# MIPI_CSI-2.net
KiCad netlist of a schematic drawn in Altium Designer
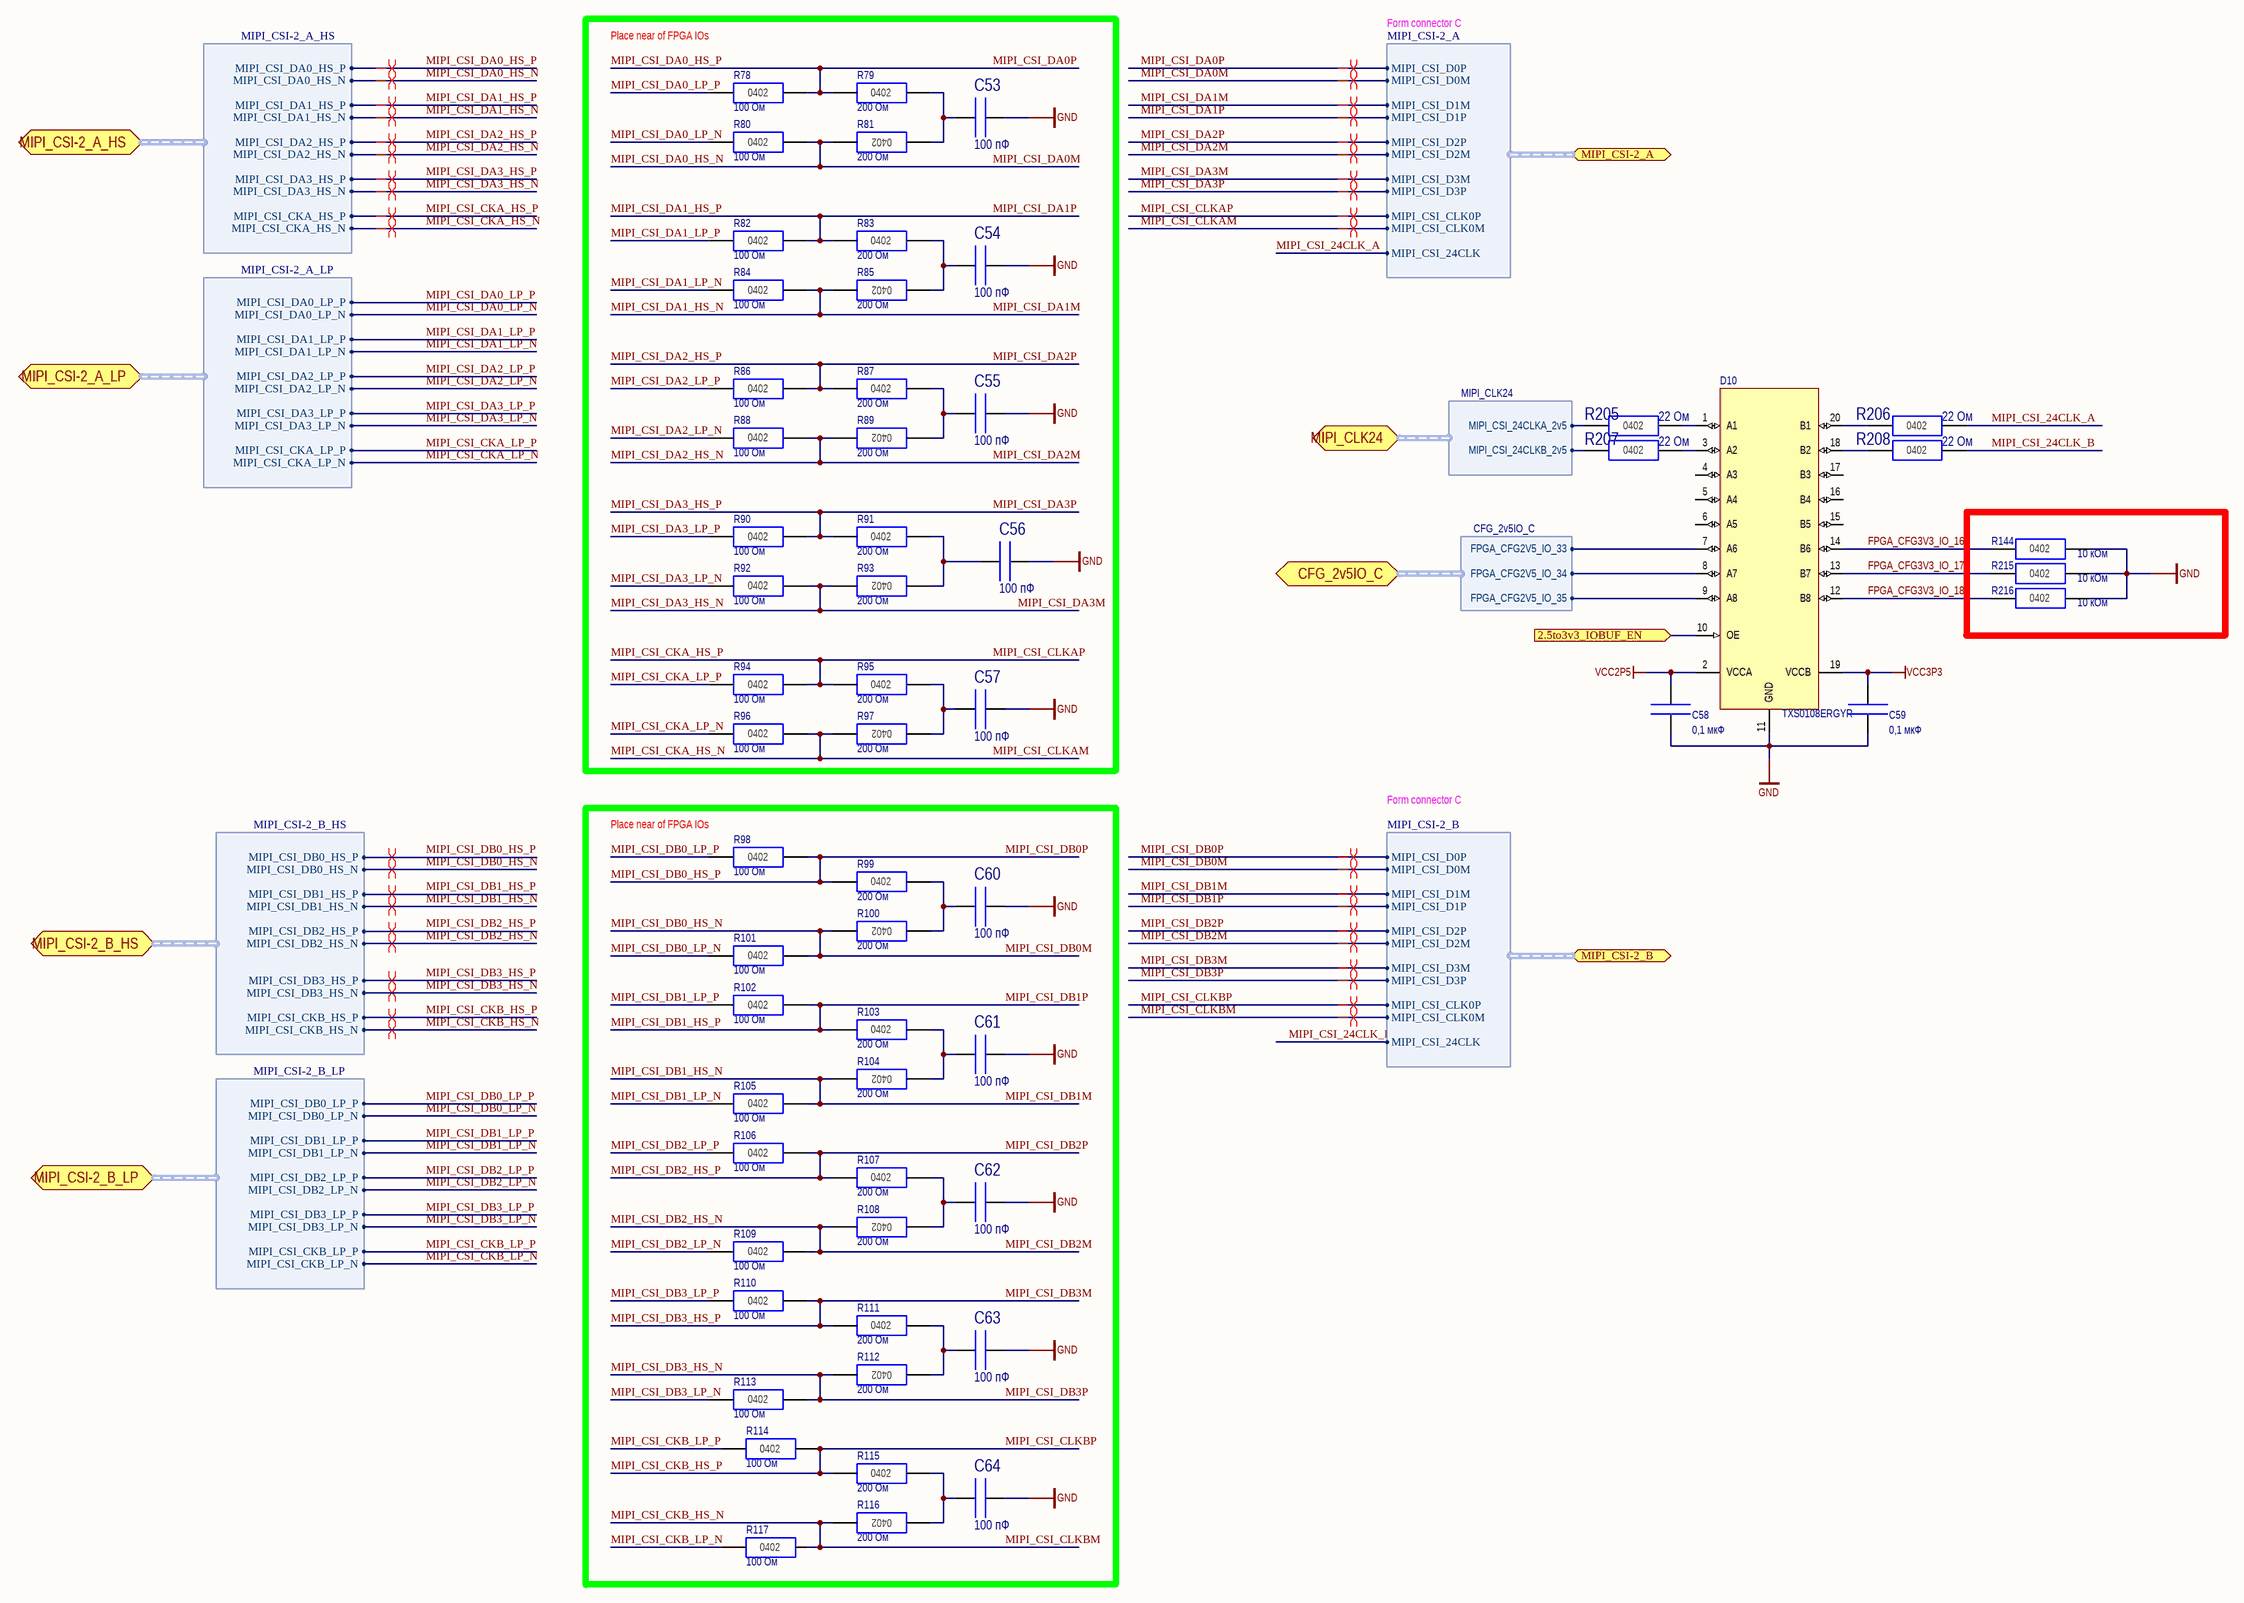
[diagram p0: MIPI_CSI-2.SchDoc]

(export (version "E")
  (design (tool "Eeschema 10.0.6"))
  (components
    (comp (ref "C53")
      (value "100 пФ")
      (footprint "CC0402(1005)")
      (description "Чип конденсатор керамический")
      (fields (field (name "Comment") "CC0402-NP0-100 пФ-1%-50В"))
      (libsource (lib "Чип конденсаторы") (part "CC0402-X7R-#-20%-10В"))
    )
    (comp (ref "C54")
      (value "100 пФ")
      (footprint "CC0402(1005)")
      (description "Чип конденсатор керамический")
      (fields (field (name "Comment") "CC0402-NP0-100 пФ-1%-50В"))
      (libsource (lib "Чип конденсаторы") (part "CC0402-X7R-#-20%-10В"))
    )
    (comp (ref "C55")
      (value "100 пФ")
      (footprint "CC0402(1005)")
      (description "Чип конденсатор керамический")
      (fields (field (name "Comment") "CC0402-NP0-100 пФ-1%-50В"))
      (libsource (lib "Чип конденсаторы") (part "CC0402-X7R-#-20%-10В"))
    )
    (comp (ref "C56")
      (value "100 пФ")
      (footprint "CC0402(1005)")
      (description "Чип конденсатор керамический")
      (fields (field (name "Comment") "CC0402-NP0-100 пФ-1%-50В"))
      (libsource (lib "Чип конденсаторы") (part "CC0402-X7R-#-20%-10В"))
    )
    (comp (ref "C57")
      (value "100 пФ")
      (footprint "CC0402(1005)")
      (description "Чип конденсатор керамический")
      (fields (field (name "Comment") "CC0402-NP0-100 пФ-1%-50В"))
      (libsource (lib "Чип конденсаторы") (part "CC0402-X7R-#-20%-10В"))
    )
    (comp (ref "C58")
      (value "0,1 мкФ")
      (footprint "CC0402(1005)")
      (description "Чип конденсатор керамический")
      (fields (field (name "Comment") "CC0402-X7R-0,1 мкФ-20%-10В"))
      (libsource (lib "Чип конденсаторы") (part "CC0402-X7R-#-20%-10В"))
    )
    (comp (ref "C59")
      (value "0,1 мкФ")
      (footprint "CC0402(1005)")
      (description "Чип конденсатор керамический")
      (fields (field (name "Comment") "CC0402-X7R-0,1 мкФ-20%-10В"))
      (libsource (lib "Чип конденсаторы") (part "CC0402-X7R-#-20%-10В"))
    )
    (comp (ref "C60")
      (value "100 пФ")
      (footprint "CC0402(1005)")
      (description "Чип конденсатор керамический")
      (fields (field (name "Comment") "CC0402-NP0-100 пФ-1%-50В"))
      (libsource (lib "Чип конденсаторы") (part "CC0402-X7R-#-20%-10В"))
    )
    (comp (ref "C61")
      (value "100 пФ")
      (footprint "CC0402(1005)")
      (description "Чип конденсатор керамический")
      (fields (field (name "Comment") "CC0402-NP0-100 пФ-1%-50В"))
      (libsource (lib "Чип конденсаторы") (part "CC0402-X7R-#-20%-10В"))
    )
    (comp (ref "C62")
      (value "100 пФ")
      (footprint "CC0402(1005)")
      (description "Чип конденсатор керамический")
      (fields (field (name "Comment") "CC0402-NP0-100 пФ-1%-50В"))
      (libsource (lib "Чип конденсаторы") (part "CC0402-X7R-#-20%-10В"))
    )
    (comp (ref "C63")
      (value "100 пФ")
      (footprint "CC0402(1005)")
      (description "Чип конденсатор керамический")
      (fields (field (name "Comment") "CC0402-NP0-100 пФ-1%-50В"))
      (libsource (lib "Чип конденсаторы") (part "CC0402-X7R-#-20%-10В"))
    )
    (comp (ref "C64")
      (value "100 пФ")
      (footprint "CC0402(1005)")
      (description "Чип конденсатор керамический")
      (fields (field (name "Comment") "CC0402-NP0-100 пФ-1%-50В"))
      (libsource (lib "Чип конденсаторы") (part "CC0402-X7R-#-20%-10В"))
    )
    (comp (ref "D10")
      (value "TXS0108ERGYR")
      (footprint "QFN50P450X350X100_HS-21N")
      (fields
        (field (name "GENERIC PART NUMBER") "TXB0108")
        (field (name "MANUFACTURER") "Texas Instruments")
      )
      (libsource (lib "SD_IC") (part "TXS0108ERGYR"))
    )
    (comp (ref "R78")
      (value "100 Ом")
      (footprint "CR0402(1005)")
      (description "Чип резистор")
      (fields (field (name "TOLERANCE") "5%") (field (name "Comment") "CR0402-100 Ом-±5%"))
      (libsource (lib "Резисторы") (part "CR0402-#-±5%"))
    )
    (comp (ref "R79")
      (value "200 Ом")
      (footprint "CR0402(1005)")
      (description "Чип резистор")
      (fields (field (name "TOLERANCE") "5%") (field (name "Comment") "CR0402-200 Ом-±5%"))
      (libsource (lib "Резисторы") (part "CR0402-#-±5%"))
    )
    (comp (ref "R80")
      (value "100 Ом")
      (footprint "CR0402(1005)")
      (description "Чип резистор")
      (fields (field (name "TOLERANCE") "5%") (field (name "Comment") "CR0402-100 Ом-±5%"))
      (libsource (lib "Резисторы") (part "CR0402-#-±5%"))
    )
    (comp (ref "R81")
      (value "200 Ом")
      (footprint "CR0402(1005)")
      (description "Чип резистор")
      (fields (field (name "TOLERANCE") "5%") (field (name "Comment") "CR0402-200 Ом-±5%"))
      (libsource (lib "") (part "CR0402-#-±5%_1"))
    )
    (comp (ref "R82")
      (value "100 Ом")
      (footprint "CR0402(1005)")
      (description "Чип резистор")
      (fields (field (name "TOLERANCE") "5%") (field (name "Comment") "CR0402-100 Ом-±5%"))
      (libsource (lib "Резисторы") (part "CR0402-#-±5%"))
    )
    (comp (ref "R83")
      (value "200 Ом")
      (footprint "CR0402(1005)")
      (description "Чип резистор")
      (fields (field (name "TOLERANCE") "5%") (field (name "Comment") "CR0402-200 Ом-±5%"))
      (libsource (lib "Резисторы") (part "CR0402-#-±5%"))
    )
    (comp (ref "R84")
      (value "100 Ом")
      (footprint "CR0402(1005)")
      (description "Чип резистор")
      (fields (field (name "TOLERANCE") "5%") (field (name "Comment") "CR0402-100 Ом-±5%"))
      (libsource (lib "Резисторы") (part "CR0402-#-±5%"))
    )
    (comp (ref "R85")
      (value "200 Ом")
      (footprint "CR0402(1005)")
      (description "Чип резистор")
      (fields (field (name "TOLERANCE") "5%") (field (name "Comment") "CR0402-200 Ом-±5%"))
      (libsource (lib "") (part "CR0402-#-±5%_1"))
    )
    (comp (ref "R86")
      (value "100 Ом")
      (footprint "CR0402(1005)")
      (description "Чип резистор")
      (fields (field (name "TOLERANCE") "5%") (field (name "Comment") "CR0402-100 Ом-±5%"))
      (libsource (lib "Резисторы") (part "CR0402-#-±5%"))
    )
    (comp (ref "R87")
      (value "200 Ом")
      (footprint "CR0402(1005)")
      (description "Чип резистор")
      (fields (field (name "TOLERANCE") "5%") (field (name "Comment") "CR0402-200 Ом-±5%"))
      (libsource (lib "Резисторы") (part "CR0402-#-±5%"))
    )
    (comp (ref "R88")
      (value "100 Ом")
      (footprint "CR0402(1005)")
      (description "Чип резистор")
      (fields (field (name "TOLERANCE") "5%") (field (name "Comment") "CR0402-100 Ом-±5%"))
      (libsource (lib "Резисторы") (part "CR0402-#-±5%"))
    )
    (comp (ref "R89")
      (value "200 Ом")
      (footprint "CR0402(1005)")
      (description "Чип резистор")
      (fields (field (name "TOLERANCE") "5%") (field (name "Comment") "CR0402-200 Ом-±5%"))
      (libsource (lib "") (part "CR0402-#-±5%_1"))
    )
    (comp (ref "R90")
      (value "100 Ом")
      (footprint "CR0402(1005)")
      (description "Чип резистор")
      (fields (field (name "TOLERANCE") "5%") (field (name "Comment") "CR0402-100 Ом-±5%"))
      (libsource (lib "Резисторы") (part "CR0402-#-±5%"))
    )
    (comp (ref "R91")
      (value "200 Ом")
      (footprint "CR0402(1005)")
      (description "Чип резистор")
      (fields (field (name "TOLERANCE") "5%") (field (name "Comment") "CR0402-200 Ом-±5%"))
      (libsource (lib "Резисторы") (part "CR0402-#-±5%"))
    )
    (comp (ref "R92")
      (value "100 Ом")
      (footprint "CR0402(1005)")
      (description "Чип резистор")
      (fields (field (name "TOLERANCE") "5%") (field (name "Comment") "CR0402-100 Ом-±5%"))
      (libsource (lib "Резисторы") (part "CR0402-#-±5%"))
    )
    (comp (ref "R93")
      (value "200 Ом")
      (footprint "CR0402(1005)")
      (description "Чип резистор")
      (fields (field (name "TOLERANCE") "5%") (field (name "Comment") "CR0402-200 Ом-±5%"))
      (libsource (lib "") (part "CR0402-#-±5%_1"))
    )
    (comp (ref "R94")
      (value "100 Ом")
      (footprint "CR0402(1005)")
      (description "Чип резистор")
      (fields (field (name "TOLERANCE") "5%") (field (name "Comment") "CR0402-100 Ом-±5%"))
      (libsource (lib "Резисторы") (part "CR0402-#-±5%"))
    )
    (comp (ref "R95")
      (value "200 Ом")
      (footprint "CR0402(1005)")
      (description "Чип резистор")
      (fields (field (name "TOLERANCE") "5%") (field (name "Comment") "CR0402-200 Ом-±5%"))
      (libsource (lib "Резисторы") (part "CR0402-#-±5%"))
    )
    (comp (ref "R96")
      (value "100 Ом")
      (footprint "CR0402(1005)")
      (description "Чип резистор")
      (fields (field (name "TOLERANCE") "5%") (field (name "Comment") "CR0402-100 Ом-±5%"))
      (libsource (lib "Резисторы") (part "CR0402-#-±5%"))
    )
    (comp (ref "R97")
      (value "200 Ом")
      (footprint "CR0402(1005)")
      (description "Чип резистор")
      (fields (field (name "TOLERANCE") "5%") (field (name "Comment") "CR0402-200 Ом-±5%"))
      (libsource (lib "") (part "CR0402-#-±5%_1"))
    )
    (comp (ref "R98")
      (value "100 Ом")
      (footprint "CR0402(1005)")
      (description "Чип резистор")
      (fields (field (name "TOLERANCE") "5%") (field (name "Comment") "CR0402-100 Ом-±5%"))
      (libsource (lib "Резисторы") (part "CR0402-#-±5%"))
    )
    (comp (ref "R99")
      (value "200 Ом")
      (footprint "CR0402(1005)")
      (description "Чип резистор")
      (fields (field (name "TOLERANCE") "5%") (field (name "Comment") "CR0402-200 Ом-±5%"))
      (libsource (lib "Резисторы") (part "CR0402-#-±5%"))
    )
    (comp (ref "R100")
      (value "200 Ом")
      (footprint "CR0402(1005)")
      (description "Чип резистор")
      (fields (field (name "TOLERANCE") "5%") (field (name "Comment") "CR0402-200 Ом-±5%"))
      (libsource (lib "") (part "CR0402-#-±5%_1"))
    )
    (comp (ref "R101")
      (value "100 Ом")
      (footprint "CR0402(1005)")
      (description "Чип резистор")
      (fields (field (name "TOLERANCE") "5%") (field (name "Comment") "CR0402-100 Ом-±5%"))
      (libsource (lib "Резисторы") (part "CR0402-#-±5%"))
    )
    (comp (ref "R102")
      (value "100 Ом")
      (footprint "CR0402(1005)")
      (description "Чип резистор")
      (fields (field (name "TOLERANCE") "5%") (field (name "Comment") "CR0402-100 Ом-±5%"))
      (libsource (lib "Резисторы") (part "CR0402-#-±5%"))
    )
    (comp (ref "R103")
      (value "200 Ом")
      (footprint "CR0402(1005)")
      (description "Чип резистор")
      (fields (field (name "TOLERANCE") "5%") (field (name "Comment") "CR0402-200 Ом-±5%"))
      (libsource (lib "Резисторы") (part "CR0402-#-±5%"))
    )
    (comp (ref "R104")
      (value "200 Ом")
      (footprint "CR0402(1005)")
      (description "Чип резистор")
      (fields (field (name "TOLERANCE") "5%") (field (name "Comment") "CR0402-200 Ом-±5%"))
      (libsource (lib "") (part "CR0402-#-±5%_1"))
    )
    (comp (ref "R105")
      (value "100 Ом")
      (footprint "CR0402(1005)")
      (description "Чип резистор")
      (fields (field (name "TOLERANCE") "5%") (field (name "Comment") "CR0402-100 Ом-±5%"))
      (libsource (lib "Резисторы") (part "CR0402-#-±5%"))
    )
    (comp (ref "R106")
      (value "100 Ом")
      (footprint "CR0402(1005)")
      (description "Чип резистор")
      (fields (field (name "TOLERANCE") "5%") (field (name "Comment") "CR0402-100 Ом-±5%"))
      (libsource (lib "Резисторы") (part "CR0402-#-±5%"))
    )
    (comp (ref "R107")
      (value "200 Ом")
      (footprint "CR0402(1005)")
      (description "Чип резистор")
      (fields (field (name "TOLERANCE") "5%") (field (name "Comment") "CR0402-200 Ом-±5%"))
      (libsource (lib "Резисторы") (part "CR0402-#-±5%"))
    )
    (comp (ref "R108")
      (value "200 Ом")
      (footprint "CR0402(1005)")
      (description "Чип резистор")
      (fields (field (name "TOLERANCE") "5%") (field (name "Comment") "CR0402-200 Ом-±5%"))
      (libsource (lib "") (part "CR0402-#-±5%_1"))
    )
    (comp (ref "R109")
      (value "100 Ом")
      (footprint "CR0402(1005)")
      (description "Чип резистор")
      (fields (field (name "TOLERANCE") "5%") (field (name "Comment") "CR0402-100 Ом-±5%"))
      (libsource (lib "Резисторы") (part "CR0402-#-±5%"))
    )
    (comp (ref "R110")
      (value "100 Ом")
      (footprint "CR0402(1005)")
      (description "Чип резистор")
      (fields (field (name "TOLERANCE") "5%") (field (name "Comment") "CR0402-100 Ом-±5%"))
      (libsource (lib "Резисторы") (part "CR0402-#-±5%"))
    )
    (comp (ref "R111")
      (value "200 Ом")
      (footprint "CR0402(1005)")
      (description "Чип резистор")
      (fields (field (name "TOLERANCE") "5%") (field (name "Comment") "CR0402-200 Ом-±5%"))
      (libsource (lib "Резисторы") (part "CR0402-#-±5%"))
    )
    (comp (ref "R112")
      (value "200 Ом")
      (footprint "CR0402(1005)")
      (description "Чип резистор")
      (fields (field (name "TOLERANCE") "5%") (field (name "Comment") "CR0402-200 Ом-±5%"))
      (libsource (lib "") (part "CR0402-#-±5%_1"))
    )
    (comp (ref "R113")
      (value "100 Ом")
      (footprint "CR0402(1005)")
      (description "Чип резистор")
      (fields (field (name "TOLERANCE") "5%") (field (name "Comment") "CR0402-100 Ом-±5%"))
      (libsource (lib "Резисторы") (part "CR0402-#-±5%"))
    )
    (comp (ref "R114")
      (value "100 Ом")
      (footprint "CR0402(1005)")
      (description "Чип резистор")
      (fields (field (name "TOLERANCE") "5%") (field (name "Comment") "CR0402-100 Ом-±5%"))
      (libsource (lib "Резисторы") (part "CR0402-#-±5%"))
    )
    (comp (ref "R115")
      (value "200 Ом")
      (footprint "CR0402(1005)")
      (description "Чип резистор")
      (fields (field (name "TOLERANCE") "5%") (field (name "Comment") "CR0402-200 Ом-±5%"))
      (libsource (lib "Резисторы") (part "CR0402-#-±5%"))
    )
    (comp (ref "R116")
      (value "200 Ом")
      (footprint "CR0402(1005)")
      (description "Чип резистор")
      (fields (field (name "TOLERANCE") "5%") (field (name "Comment") "CR0402-200 Ом-±5%"))
      (libsource (lib "") (part "CR0402-#-±5%_1"))
    )
    (comp (ref "R117")
      (value "100 Ом")
      (footprint "CR0402(1005)")
      (description "Чип резистор")
      (fields (field (name "TOLERANCE") "5%") (field (name "Comment") "CR0402-100 Ом-±5%"))
      (libsource (lib "Резисторы") (part "CR0402-#-±5%"))
    )
    (comp (ref "R144")
      (value "10 кОм")
      (footprint "CR0402(1005)")
      (description "Чип резистор")
      (fields (field (name "TOLERANCE") "5%") (field (name "Comment") "CR0402-10 кОм-±5%"))
      (libsource (lib "Резисторы") (part "CR0402-#-±5%"))
    )
    (comp (ref "R205")
      (value "22 Ом")
      (footprint "CR0402(1005)")
      (description "Чип резистор")
      (fields (field (name "TOLERANCE") "5%") (field (name "Comment") "CR0402-22 Ом-±5%"))
      (libsource (lib "Чип резисторы") (part "CR0402-#-±5%"))
    )
    (comp (ref "R206")
      (value "22 Ом")
      (footprint "CR0402(1005)")
      (description "Чип резистор")
      (fields (field (name "TOLERANCE") "5%") (field (name "Comment") "CR0402-22 Ом-±5%"))
      (libsource (lib "Чип резисторы") (part "CR0402-#-±5%"))
    )
    (comp (ref "R207")
      (value "22 Ом")
      (footprint "CR0402(1005)")
      (description "Чип резистор")
      (fields (field (name "TOLERANCE") "5%") (field (name "Comment") "CR0402-22 Ом-±5%"))
      (libsource (lib "Чип резисторы") (part "CR0402-#-±5%"))
    )
    (comp (ref "R208")
      (value "22 Ом")
      (footprint "CR0402(1005)")
      (description "Чип резистор")
      (fields (field (name "TOLERANCE") "5%") (field (name "Comment") "CR0402-22 Ом-±5%"))
      (libsource (lib "Чип резисторы") (part "CR0402-#-±5%"))
    )
    (comp (ref "R215")
      (value "10 кОм")
      (footprint "CR0402(1005)")
      (description "Чип резистор")
      (fields (field (name "TOLERANCE") "5%") (field (name "Comment") "CR0402-10 кОм-±5%"))
      (libsource (lib "Резисторы") (part "CR0402-#-±5%"))
    )
    (comp (ref "R216")
      (value "10 кОм")
      (footprint "CR0402(1005)")
      (description "Чип резистор")
      (fields (field (name "TOLERANCE") "5%") (field (name "Comment") "CR0402-10 кОм-±5%"))
      (libsource (lib "Резисторы") (part "CR0402-#-±5%"))
    )
  )
  (nets
    (net (code "9") (name "/2.5to3v3_IOBUF_EN") (class "Default")
      (node (ref "D10") (pin "10") (pinfunction "OE_10") (pintype "input"))
    )
    (net (code "10") (name "/FPGA_CFG2V5_IO_33") (class "Default")
      (node (ref "D10") (pin "7") (pinfunction "A6_7") (pintype "bidirectional"))
    )
    (net (code "11") (name "/FPGA_CFG2V5_IO_34") (class "Default")
      (node (ref "D10") (pin "8") (pinfunction "A7_8") (pintype "bidirectional"))
    )
    (net (code "12") (name "/FPGA_CFG2V5_IO_35") (class "Default")
      (node (ref "D10") (pin "9") (pinfunction "A8_9") (pintype "bidirectional"))
    )
    (net (code "13") (name "/FPGA_CFG3V3_IO_16") (class "Default")
      (node (ref "D10") (pin "14") (pinfunction "B6_14") (pintype "bidirectional"))
      (node (ref "R144") (pin "1") (pinfunction "+_1") (pintype "passive"))
    )
    (net (code "14") (name "/FPGA_CFG3V3_IO_17") (class "Default")
      (node (ref "D10") (pin "13") (pinfunction "B7_13") (pintype "bidirectional"))
      (node (ref "R215") (pin "1") (pinfunction "+_1") (pintype "passive"))
    )
    (net (code "15") (name "/FPGA_CFG3V3_IO_18") (class "Default")
      (node (ref "D10") (pin "12") (pinfunction "B8_12") (pintype "bidirectional"))
      (node (ref "R216") (pin "1") (pinfunction "+_1") (pintype "passive"))
    )
    (net (code "16") (name "/MIPI_CSI_24CLKA_2v5") (class "Default")
      (node (ref "R205") (pin "1") (pinfunction "+_1") (pintype "passive"))
    )
    (net (code "17") (name "/MIPI_CSI_24CLKB_2v5") (class "Default")
      (node (ref "R207") (pin "1") (pinfunction "+_1") (pintype "passive"))
    )
    (net (code "18") (name "/MIPI_CSI_24CLK_A") (class "Default")
      (node (ref "R206") (pin "2") (pinfunction "-_2") (pintype "passive"))
    )
    (net (code "19") (name "/MIPI_CSI_24CLK_B") (class "Default")
      (node (ref "R208") (pin "2") (pinfunction "-_2") (pintype "passive"))
    )
    (net (code "20") (name "/MIPI_CSI_CKA_HS_N") (class "Default")
      (node (ref "R96") (pin "2") (pinfunction "-_2") (pintype "passive"))
      (node (ref "R97") (pin "2") (pinfunction "-_2") (pintype "passive"))
    )
    (net (code "21") (name "/MIPI_CSI_CKA_HS_P") (class "Default")
      (node (ref "R94") (pin "2") (pinfunction "-_2") (pintype "passive"))
      (node (ref "R95") (pin "1") (pinfunction "+_1") (pintype "passive"))
    )
    (net (code "22") (name "/MIPI_CSI_CKA_LP_N") (class "Default")
      (node (ref "R96") (pin "1") (pinfunction "+_1") (pintype "passive"))
    )
    (net (code "23") (name "/MIPI_CSI_CKA_LP_P") (class "Default")
      (node (ref "R94") (pin "1") (pinfunction "+_1") (pintype "passive"))
    )
    (net (code "24") (name "/MIPI_CSI_CKB_HS_N") (class "Default")
      (node (ref "R116") (pin "2") (pinfunction "-_2") (pintype "passive"))
      (node (ref "R117") (pin "2") (pinfunction "-_2") (pintype "passive"))
    )
    (net (code "25") (name "/MIPI_CSI_CKB_HS_P") (class "Default")
      (node (ref "R114") (pin "2") (pinfunction "-_2") (pintype "passive"))
      (node (ref "R115") (pin "1") (pinfunction "+_1") (pintype "passive"))
    )
    (net (code "26") (name "/MIPI_CSI_CKB_LP_N") (class "Default")
      (node (ref "R117") (pin "1") (pinfunction "+_1") (pintype "passive"))
    )
    (net (code "27") (name "/MIPI_CSI_CKB_LP_P") (class "Default")
      (node (ref "R114") (pin "1") (pinfunction "+_1") (pintype "passive"))
    )
    (net (code "28") (name "/MIPI_CSI_DA0M") (class "Default")
      (node (ref "R80") (pin "2") (pinfunction "-_2") (pintype "passive"))
      (node (ref "R81") (pin "2") (pinfunction "-_2") (pintype "passive"))
    )
    (net (code "29") (name "/MIPI_CSI_DA0P") (class "Default")
      (node (ref "R78") (pin "2") (pinfunction "-_2") (pintype "passive"))
      (node (ref "R79") (pin "1") (pinfunction "+_1") (pintype "passive"))
    )
    (net (code "30") (name "/MIPI_CSI_DA0_LP_N") (class "Default")
      (node (ref "R80") (pin "1") (pinfunction "+_1") (pintype "passive"))
    )
    (net (code "31") (name "/MIPI_CSI_DA0_LP_P") (class "Default")
      (node (ref "R78") (pin "1") (pinfunction "+_1") (pintype "passive"))
    )
    (net (code "32") (name "/MIPI_CSI_DA1M") (class "Default")
      (node (ref "R84") (pin "2") (pinfunction "-_2") (pintype "passive"))
      (node (ref "R85") (pin "2") (pinfunction "-_2") (pintype "passive"))
    )
    (net (code "33") (name "/MIPI_CSI_DA1P") (class "Default")
      (node (ref "R82") (pin "2") (pinfunction "-_2") (pintype "passive"))
      (node (ref "R83") (pin "1") (pinfunction "+_1") (pintype "passive"))
    )
    (net (code "34") (name "/MIPI_CSI_DA1_LP_N") (class "Default")
      (node (ref "R84") (pin "1") (pinfunction "+_1") (pintype "passive"))
    )
    (net (code "35") (name "/MIPI_CSI_DA1_LP_P") (class "Default")
      (node (ref "R82") (pin "1") (pinfunction "+_1") (pintype "passive"))
    )
    (net (code "36") (name "/MIPI_CSI_DA2M") (class "Default")
      (node (ref "R88") (pin "2") (pinfunction "-_2") (pintype "passive"))
      (node (ref "R89") (pin "2") (pinfunction "-_2") (pintype "passive"))
    )
    (net (code "37") (name "/MIPI_CSI_DA2P") (class "Default")
      (node (ref "R86") (pin "2") (pinfunction "-_2") (pintype "passive"))
      (node (ref "R87") (pin "1") (pinfunction "+_1") (pintype "passive"))
    )
    (net (code "38") (name "/MIPI_CSI_DA2_LP_N") (class "Default")
      (node (ref "R88") (pin "1") (pinfunction "+_1") (pintype "passive"))
    )
    (net (code "39") (name "/MIPI_CSI_DA2_LP_P") (class "Default")
      (node (ref "R86") (pin "1") (pinfunction "+_1") (pintype "passive"))
    )
    (net (code "40") (name "/MIPI_CSI_DA3M") (class "Default")
      (node (ref "R92") (pin "2") (pinfunction "-_2") (pintype "passive"))
      (node (ref "R93") (pin "2") (pinfunction "-_2") (pintype "passive"))
    )
    (net (code "41") (name "/MIPI_CSI_DA3P") (class "Default")
      (node (ref "R90") (pin "2") (pinfunction "-_2") (pintype "passive"))
      (node (ref "R91") (pin "1") (pinfunction "+_1") (pintype "passive"))
    )
    (net (code "42") (name "/MIPI_CSI_DA3_LP_N") (class "Default")
      (node (ref "R92") (pin "1") (pinfunction "+_1") (pintype "passive"))
    )
    (net (code "43") (name "/MIPI_CSI_DA3_LP_P") (class "Default")
      (node (ref "R90") (pin "1") (pinfunction "+_1") (pintype "passive"))
    )
    (net (code "44") (name "/MIPI_CSI_DB0M") (class "Default")
      (node (ref "R100") (pin "2") (pinfunction "-_2") (pintype "passive"))
      (node (ref "R101") (pin "2") (pinfunction "-_2") (pintype "passive"))
    )
    (net (code "45") (name "/MIPI_CSI_DB0P") (class "Default")
      (node (ref "R98") (pin "2") (pinfunction "-_2") (pintype "passive"))
      (node (ref "R99") (pin "1") (pinfunction "+_1") (pintype "passive"))
    )
    (net (code "46") (name "/MIPI_CSI_DB0_LP_N") (class "Default")
      (node (ref "R101") (pin "1") (pinfunction "+_1") (pintype "passive"))
    )
    (net (code "47") (name "/MIPI_CSI_DB0_LP_P") (class "Default")
      (node (ref "R98") (pin "1") (pinfunction "+_1") (pintype "passive"))
    )
    (net (code "48") (name "/MIPI_CSI_DB1M") (class "Default")
      (node (ref "R104") (pin "2") (pinfunction "-_2") (pintype "passive"))
      (node (ref "R105") (pin "2") (pinfunction "-_2") (pintype "passive"))
    )
    (net (code "49") (name "/MIPI_CSI_DB1P") (class "Default")
      (node (ref "R102") (pin "2") (pinfunction "-_2") (pintype "passive"))
      (node (ref "R103") (pin "1") (pinfunction "+_1") (pintype "passive"))
    )
    (net (code "50") (name "/MIPI_CSI_DB1_LP_N") (class "Default")
      (node (ref "R105") (pin "1") (pinfunction "+_1") (pintype "passive"))
    )
    (net (code "51") (name "/MIPI_CSI_DB1_LP_P") (class "Default")
      (node (ref "R102") (pin "1") (pinfunction "+_1") (pintype "passive"))
    )
    (net (code "52") (name "/MIPI_CSI_DB2M") (class "Default")
      (node (ref "R108") (pin "2") (pinfunction "-_2") (pintype "passive"))
      (node (ref "R109") (pin "2") (pinfunction "-_2") (pintype "passive"))
    )
    (net (code "53") (name "/MIPI_CSI_DB2P") (class "Default")
      (node (ref "R106") (pin "2") (pinfunction "-_2") (pintype "passive"))
      (node (ref "R107") (pin "1") (pinfunction "+_1") (pintype "passive"))
    )
    (net (code "54") (name "/MIPI_CSI_DB2_LP_N") (class "Default")
      (node (ref "R109") (pin "1") (pinfunction "+_1") (pintype "passive"))
    )
    (net (code "55") (name "/MIPI_CSI_DB2_LP_P") (class "Default")
      (node (ref "R106") (pin "1") (pinfunction "+_1") (pintype "passive"))
    )
    (net (code "56") (name "/MIPI_CSI_DB3M") (class "Default")
      (node (ref "R110") (pin "2") (pinfunction "-_2") (pintype "passive"))
      (node (ref "R111") (pin "1") (pinfunction "+_1") (pintype "passive"))
    )
    (net (code "57") (name "/MIPI_CSI_DB3P") (class "Default")
      (node (ref "R112") (pin "2") (pinfunction "-_2") (pintype "passive"))
      (node (ref "R113") (pin "2") (pinfunction "-_2") (pintype "passive"))
    )
    (net (code "58") (name "/MIPI_CSI_DB3_LP_N") (class "Default")
      (node (ref "R113") (pin "1") (pinfunction "+_1") (pintype "passive"))
    )
    (net (code "59") (name "/MIPI_CSI_DB3_LP_P") (class "Default")
      (node (ref "R110") (pin "1") (pinfunction "+_1") (pintype "passive"))
    )
    (net (code "68") (name "GND") (class "Default")
      (node (ref "C53") (pin "1") (pinfunction "+_1") (pintype "passive"))
      (node (ref "C54") (pin "1") (pinfunction "+_1") (pintype "passive"))
      (node (ref "C55") (pin "1") (pinfunction "+_1") (pintype "passive"))
      (node (ref "C56") (pin "1") (pinfunction "+_1") (pintype "passive"))
      (node (ref "C57") (pin "1") (pinfunction "+_1") (pintype "passive"))
      (node (ref "C58") (pin "2") (pinfunction "-_2") (pintype "passive"))
      (node (ref "C59") (pin "2") (pinfunction "-_2") (pintype "passive"))
      (node (ref "C60") (pin "1") (pinfunction "+_1") (pintype "passive"))
      (node (ref "C61") (pin "1") (pinfunction "+_1") (pintype "passive"))
      (node (ref "C62") (pin "1") (pinfunction "+_1") (pintype "passive"))
      (node (ref "C63") (pin "1") (pinfunction "+_1") (pintype "passive"))
      (node (ref "C64") (pin "1") (pinfunction "+_1") (pintype "passive"))
      (node (ref "D10") (pin "11") (pinfunction "GND_11") (pintype "power_in"))
      (node (ref "R144") (pin "2") (pinfunction "-_2") (pintype "passive"))
      (node (ref "R215") (pin "2") (pinfunction "-_2") (pintype "passive"))
      (node (ref "R216") (pin "2") (pinfunction "-_2") (pintype "passive"))
    )
    (net (code "69") (name "Net-(C53--)") (class "Default")
      (node (ref "C53") (pin "2") (pinfunction "-_2") (pintype "passive"))
      (node (ref "R79") (pin "2") (pinfunction "-_2") (pintype "passive"))
      (node (ref "R81") (pin "1") (pinfunction "+_1") (pintype "passive"))
    )
    (net (code "70") (name "Net-(C54--)") (class "Default")
      (node (ref "C54") (pin "2") (pinfunction "-_2") (pintype "passive"))
      (node (ref "R83") (pin "2") (pinfunction "-_2") (pintype "passive"))
      (node (ref "R85") (pin "1") (pinfunction "+_1") (pintype "passive"))
    )
    (net (code "71") (name "Net-(C55--)") (class "Default")
      (node (ref "C55") (pin "2") (pinfunction "-_2") (pintype "passive"))
      (node (ref "R87") (pin "2") (pinfunction "-_2") (pintype "passive"))
      (node (ref "R89") (pin "1") (pinfunction "+_1") (pintype "passive"))
    )
    (net (code "72") (name "Net-(C56--)") (class "Default")
      (node (ref "C56") (pin "2") (pinfunction "-_2") (pintype "passive"))
      (node (ref "R91") (pin "2") (pinfunction "-_2") (pintype "passive"))
      (node (ref "R93") (pin "1") (pinfunction "+_1") (pintype "passive"))
    )
    (net (code "73") (name "Net-(C57--)") (class "Default")
      (node (ref "C57") (pin "2") (pinfunction "-_2") (pintype "passive"))
      (node (ref "R95") (pin "2") (pinfunction "-_2") (pintype "passive"))
      (node (ref "R97") (pin "1") (pinfunction "+_1") (pintype "passive"))
    )
    (net (code "74") (name "Net-(C60--)") (class "Default")
      (node (ref "C60") (pin "2") (pinfunction "-_2") (pintype "passive"))
      (node (ref "R100") (pin "1") (pinfunction "+_1") (pintype "passive"))
      (node (ref "R99") (pin "2") (pinfunction "-_2") (pintype "passive"))
    )
    (net (code "75") (name "Net-(C61--)") (class "Default")
      (node (ref "C61") (pin "2") (pinfunction "-_2") (pintype "passive"))
      (node (ref "R103") (pin "2") (pinfunction "-_2") (pintype "passive"))
      (node (ref "R104") (pin "1") (pinfunction "+_1") (pintype "passive"))
    )
    (net (code "76") (name "Net-(C62--)") (class "Default")
      (node (ref "C62") (pin "2") (pinfunction "-_2") (pintype "passive"))
      (node (ref "R107") (pin "2") (pinfunction "-_2") (pintype "passive"))
      (node (ref "R108") (pin "1") (pinfunction "+_1") (pintype "passive"))
    )
    (net (code "77") (name "Net-(C63--)") (class "Default")
      (node (ref "C63") (pin "2") (pinfunction "-_2") (pintype "passive"))
      (node (ref "R111") (pin "2") (pinfunction "-_2") (pintype "passive"))
      (node (ref "R112") (pin "1") (pinfunction "+_1") (pintype "passive"))
    )
    (net (code "78") (name "Net-(C64--)") (class "Default")
      (node (ref "C64") (pin "2") (pinfunction "-_2") (pintype "passive"))
      (node (ref "R115") (pin "2") (pinfunction "-_2") (pintype "passive"))
      (node (ref "R116") (pin "1") (pinfunction "+_1") (pintype "passive"))
    )
    (net (code "79") (name "Net-(D10-A1)") (class "Default")
      (node (ref "D10") (pin "1") (pinfunction "A1_1") (pintype "bidirectional"))
      (node (ref "R205") (pin "2") (pinfunction "-_2") (pintype "passive"))
    )
    (net (code "80") (name "Net-(D10-A2)") (class "Default")
      (node (ref "D10") (pin "3") (pinfunction "A2_3") (pintype "bidirectional"))
      (node (ref "R207") (pin "2") (pinfunction "-_2") (pintype "passive"))
    )
    (net (code "81") (name "Net-(D10-B1)") (class "Default")
      (node (ref "D10") (pin "20") (pinfunction "B1_20") (pintype "bidirectional"))
      (node (ref "R206") (pin "1") (pinfunction "+_1") (pintype "passive"))
    )
    (net (code "82") (name "Net-(D10-B2)") (class "Default")
      (node (ref "D10") (pin "18") (pinfunction "B2_18") (pintype "bidirectional"))
      (node (ref "R208") (pin "1") (pinfunction "+_1") (pintype "passive"))
    )
    (net (code "83") (name "VCC2P5") (class "Default")
      (node (ref "C58") (pin "1") (pinfunction "+_1") (pintype "passive"))
      (node (ref "D10") (pin "2") (pinfunction "VCCA_2") (pintype "power_in"))
    )
    (net (code "84") (name "VCC3P3") (class "Default")
      (node (ref "C59") (pin "1") (pinfunction "+_1") (pintype "passive"))
      (node (ref "D10") (pin "19") (pinfunction "VCCB_19") (pintype "power_in"))
    )
    (net (code "85") (name "unconnected-(D10-A3-Pad4)") (class "Default")
      (node (ref "D10") (pin "4") (pinfunction "A3_4") (pintype "bidirectional"))
    )
    (net (code "86") (name "unconnected-(D10-A4-Pad5)") (class "Default")
      (node (ref "D10") (pin "5") (pinfunction "A4_5") (pintype "bidirectional"))
    )
    (net (code "87") (name "unconnected-(D10-A5-Pad6)") (class "Default")
      (node (ref "D10") (pin "6") (pinfunction "A5_6") (pintype "bidirectional"))
    )
    (net (code "88") (name "unconnected-(D10-B3-Pad17)") (class "Default")
      (node (ref "D10") (pin "17") (pinfunction "B3_17") (pintype "bidirectional"))
    )
    (net (code "89") (name "unconnected-(D10-B4-Pad16)") (class "Default")
      (node (ref "D10") (pin "16") (pinfunction "B4_16") (pintype "bidirectional"))
    )
    (net (code "90") (name "unconnected-(D10-B5-Pad15)") (class "Default")
      (node (ref "D10") (pin "15") (pinfunction "B5_15") (pintype "bidirectional"))
    )
  )
)
